# Sheet1.net
KiCad netlist of a schematic drawn in Altium Designer
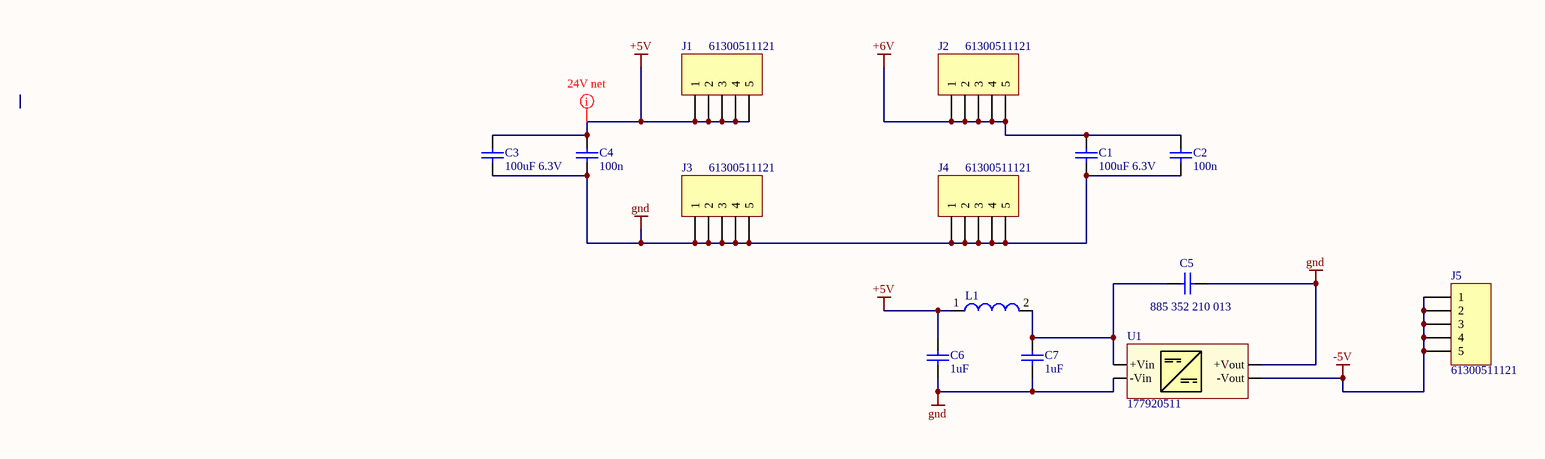
[diagram p0: Sheet1.SchDoc]

(export (version "E")
  (design (tool "Eeschema 10.0.6"))
  (components
    (comp (ref "C1")
      (value "100uF 6.3V")
      (footprint "CAPC1206(3216)190_L")
      (description "CAP 100uF 6.3V ±20% 1206 (3216 Metric) Thickness 1.9mm SMD")
      (fields (field (name "TOLERANCE") "Â±20%"))
      (libsource (lib "Altium Vault EMBL") (part "CMP-00469-1"))
    )
    (comp (ref "C2")
      (value "100n")
      (footprint "CAPC2013X88X50ML20T25")
      (description "generic 0805 COG oder X7R Vielschichtkondensatoren max. +/-10%")
      (libsource (lib "Altium Vault EMBL") (part "CMP-001-0082-2"))
    )
    (comp (ref "C3")
      (value "100uF 6.3V")
      (footprint "CAPC1206(3216)190_L")
      (description "CAP 100uF 6.3V ±20% 1206 (3216 Metric) Thickness 1.9mm SMD")
      (fields (field (name "TOLERANCE") "Â±20%"))
      (libsource (lib "Altium Vault EMBL") (part "CMP-00469-1"))
    )
    (comp (ref "C4")
      (value "100n")
      (footprint "CAPC2013X88X50ML20T25")
      (description "generic 0805 COG oder X7R Vielschichtkondensatoren max. +/-10%")
      (libsource (lib "Altium Vault EMBL") (part "CMP-001-0082-2"))
    )
    (comp (ref "C5")
      (value "885 352 210 013")
      (footprint "CAPC1808(4520)215_M")
      (description "1,0nF  1808  250V")
      (fields (field (name "MANUFACTURER") "Wurth Electronics Inc.") (field (name "TOLERANCE") "±10%"))
      (libsource (lib "Altium Vault EMBL") (part "CMP-001-0032-3"))
    )
    (comp (ref "C6")
      (value "1uF")
      (footprint "CAPC1206(3216)190_N")
      (description "CAP CER 1UF 10V X7R 1206")
      (fields
        (field (name "MANUFACTURER") "Wurth Electronics Inc.")
        (field (name "MANUFACTURER PART NUMBER") "885012208013")
      )
      (libsource (lib "Altium Vault EMBL") (part "CMP-001-0138-A.1"))
    )
    (comp (ref "C7")
      (value "1uF")
      (footprint "CAPC1206(3216)190_N")
      (description "CAP CER 1UF 10V X7R 1206")
      (fields
        (field (name "MANUFACTURER") "Wurth Electronics Inc.")
        (field (name "MANUFACTURER PART NUMBER") "885012208013")
      )
      (libsource (lib "Altium Vault EMBL") (part "CMP-001-0138-A.1"))
    )
    (comp (ref "J1")
      (value "61300511121")
      (footprint "61300411121")
      (description "5Pol; gerade; WR-PHD 2.54 mm THT Pin Header")
      (fields (field (name "MANUFACTURER") "Wurth Electronics"))
      (libsource (lib "Altium Vault EMBL") (part "CMP-001-0074-1"))
    )
    (comp (ref "J2")
      (value "61300511121")
      (footprint "61300411121")
      (description "5Pol; gerade; WR-PHD 2.54 mm THT Pin Header")
      (fields (field (name "MANUFACTURER") "Wurth Electronics"))
      (libsource (lib "Altium Vault EMBL") (part "CMP-001-0074-1"))
    )
    (comp (ref "J3")
      (value "61300511121")
      (footprint "61300411121")
      (description "5Pol; gerade; WR-PHD 2.54 mm THT Pin Header")
      (fields (field (name "MANUFACTURER") "Wurth Electronics"))
      (libsource (lib "Altium Vault EMBL") (part "CMP-001-0074-1"))
    )
    (comp (ref "J4")
      (value "61300511121")
      (footprint "61300411121")
      (description "5Pol; gerade; WR-PHD 2.54 mm THT Pin Header")
      (fields (field (name "MANUFACTURER") "Wurth Electronics"))
      (libsource (lib "Altium Vault EMBL") (part "CMP-001-0074-1"))
    )
    (comp (ref "J5")
      (value "61300511121")
      (footprint "61300411121")
      (description "5Pol; gerade; WR-PHD 2.54 mm THT Pin Header")
      (fields (field (name "MANUFACTURER") "Wurth Electronics"))
      (libsource (lib "Altium Vault EMBL 3") (part "CMP-001-0074-1"))
    )
    (comp (ref "L1")
      (value "WE - 744773168")
      (footprint "WE-PD2-S")
      (description "WE-PD2 SMD-Speicherdrossel; 68uH; 0,68A; L = 68 μH ±10%; IR = 0.56A; Isat = 0.68 A; RDC = 1.117 Ω")
      (fields (field (name "PARTNUMBER") "744773168") (field (name "MANUFACTURER") "Wurth Electronics"))
      (libsource (lib "Altium Vault EMBL") (part "CMP-001-0054-3"))
    )
    (comp (ref "U1")
      (value "177920511")
      (footprint "WE-FSIM-SIP-4")
      (fields
        (field (name "MANUFACTURER") "Wurth Electronics Inc.")
        (field (name "PARTNUMBER") "177 920 511")
      )
      (libsource (lib "Altium Vault EMBL") (part "CMP-001-0110-A.2"))
    )
  )
  (nets
    (net (code "1") (name "+5V") (class "Default")
      (node (ref "C3") (pin "2") (pinfunction "2_2") (pintype "passive"))
      (node (ref "C4") (pin "2") (pinfunction "2_2") (pintype "passive"))
      (node (ref "C6") (pin "2") (pinfunction "2_2") (pintype "passive"))
      (node (ref "J1") (pin "1") (pinfunction "1_1") (pintype "passive"))
      (node (ref "J1") (pin "2") (pinfunction "2_2") (pintype "passive"))
      (node (ref "J1") (pin "3") (pinfunction "3_3") (pintype "passive"))
      (node (ref "J1") (pin "4") (pinfunction "4_4") (pintype "passive"))
      (node (ref "J1") (pin "5") (pinfunction "5_5") (pintype "passive"))
      (node (ref "L1") (pin "1") (pinfunction "1_1") (pintype "passive"))
    )
    (net (code "2") (name "+6V") (class "Default")
      (node (ref "C1") (pin "2") (pinfunction "2_2") (pintype "passive"))
      (node (ref "C2") (pin "2") (pinfunction "2_2") (pintype "passive"))
      (node (ref "J2") (pin "1") (pinfunction "1_1") (pintype "passive"))
      (node (ref "J2") (pin "2") (pinfunction "2_2") (pintype "passive"))
      (node (ref "J2") (pin "3") (pinfunction "3_3") (pintype "passive"))
      (node (ref "J2") (pin "4") (pinfunction "4_4") (pintype "passive"))
      (node (ref "J2") (pin "5") (pinfunction "5_5") (pintype "passive"))
    )
    (net (code "3") (name "-5V") (class "Default")
      (node (ref "J5") (pin "1") (pinfunction "1_1") (pintype "passive"))
      (node (ref "J5") (pin "2") (pinfunction "2_2") (pintype "passive"))
      (node (ref "J5") (pin "3") (pinfunction "3_3") (pintype "passive"))
      (node (ref "J5") (pin "4") (pinfunction "4_4") (pintype "passive"))
      (node (ref "J5") (pin "5") (pinfunction "5_5") (pintype "passive"))
      (node (ref "U1") (pin "3") (pinfunction "-Vout_3") (pintype "power_in"))
    )
    (net (code "4") (name "Net-(U1-+Vin)") (class "Default")
      (node (ref "C5") (pin "1") (pinfunction "1_1") (pintype "passive"))
      (node (ref "C7") (pin "2") (pinfunction "2_2") (pintype "passive"))
      (node (ref "L1") (pin "2") (pinfunction "2_2") (pintype "passive"))
      (node (ref "U1") (pin "2") (pinfunction "+Vin_2") (pintype "passive"))
    )
    (net (code "5") (name "gnd") (class "Default")
      (node (ref "C1") (pin "1") (pinfunction "1_1") (pintype "passive"))
      (node (ref "C2") (pin "1") (pinfunction "1_1") (pintype "passive"))
      (node (ref "C3") (pin "1") (pinfunction "1_1") (pintype "passive"))
      (node (ref "C4") (pin "1") (pinfunction "1_1") (pintype "passive"))
      (node (ref "C5") (pin "2") (pinfunction "2_2") (pintype "passive"))
      (node (ref "C6") (pin "1") (pinfunction "1_1") (pintype "passive"))
      (node (ref "C7") (pin "1") (pinfunction "1_1") (pintype "passive"))
      (node (ref "J3") (pin "1") (pinfunction "1_1") (pintype "passive"))
      (node (ref "J3") (pin "2") (pinfunction "2_2") (pintype "passive"))
      (node (ref "J3") (pin "3") (pinfunction "3_3") (pintype "passive"))
      (node (ref "J3") (pin "4") (pinfunction "4_4") (pintype "passive"))
      (node (ref "J3") (pin "5") (pinfunction "5_5") (pintype "passive"))
      (node (ref "J4") (pin "1") (pinfunction "1_1") (pintype "passive"))
      (node (ref "J4") (pin "2") (pinfunction "2_2") (pintype "passive"))
      (node (ref "J4") (pin "3") (pinfunction "3_3") (pintype "passive"))
      (node (ref "J4") (pin "4") (pinfunction "4_4") (pintype "passive"))
      (node (ref "J4") (pin "5") (pinfunction "5_5") (pintype "passive"))
      (node (ref "U1") (pin "1") (pinfunction "-Vin_1") (pintype "passive"))
      (node (ref "U1") (pin "4") (pinfunction "+Vout_4") (pintype "passive"))
    )
  )
)
